# PIC_WIFI.net
KiCad netlist of a schematic drawn in EAGLE
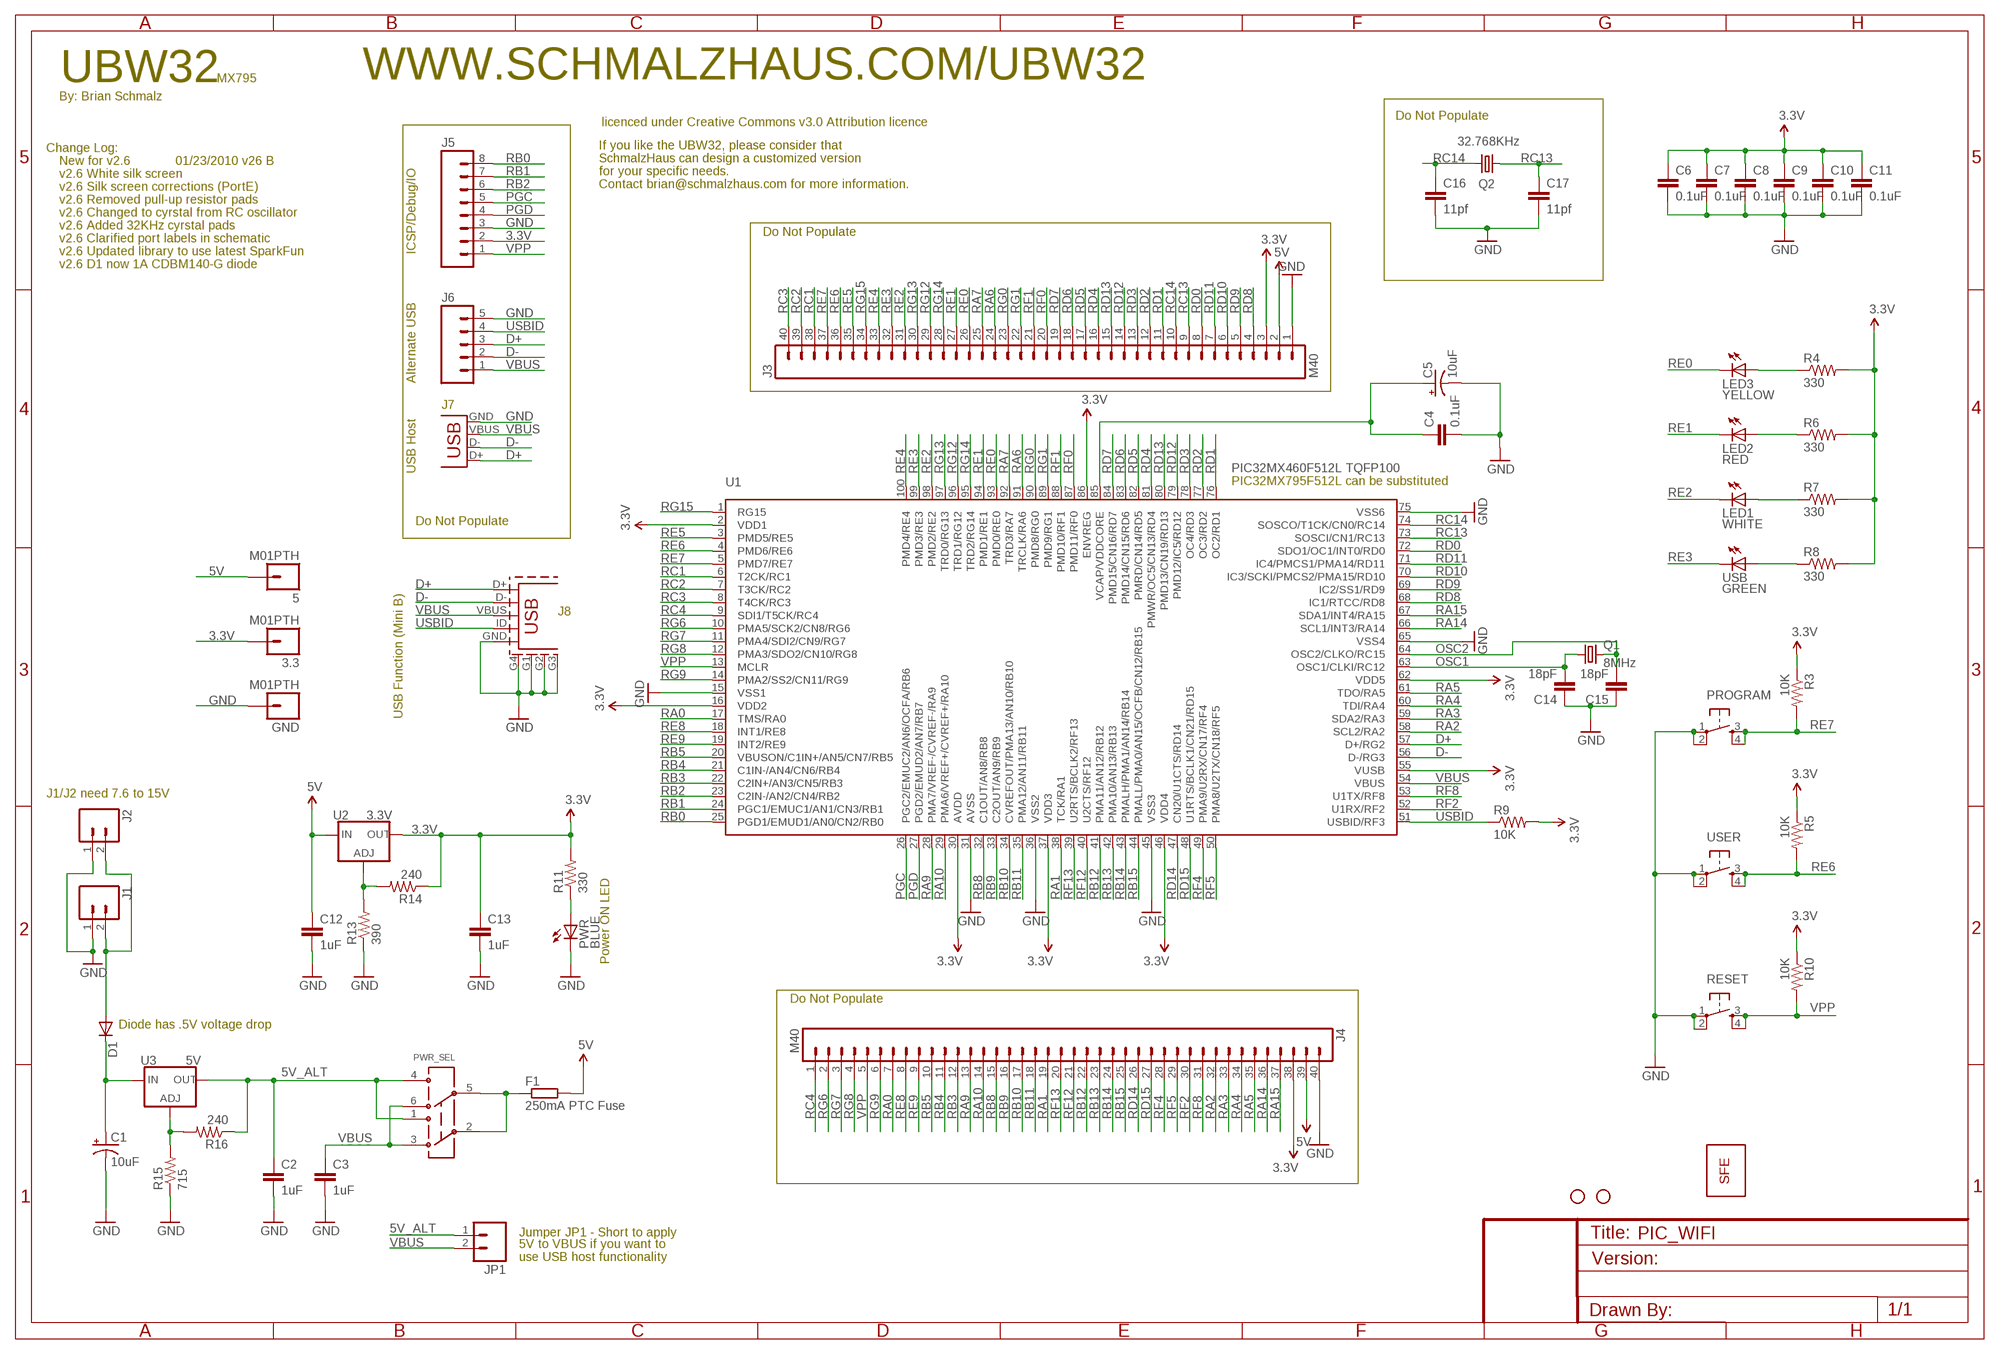
[diagram p0: schematic, sheet 1]

(export (version "E")
  (design (tool "Eeschema 10.0.6"))
  (components
    (comp (ref "3.3")
      (value "M01PTH")
      (footprint "eagle-import:1X01")
      (libsource (lib "eagle-import") (part "M01PTH"))
    )
    (comp (ref "5")
      (value "M01PTH")
      (footprint "eagle-import:1X01")
      (libsource (lib "eagle-import") (part "M01PTH"))
    )
    (comp (ref "C1")
      (value "10uF")
      (footprint "eagle-import:EIA3528")
      (libsource (lib "eagle-import") (part "CAP_POL3528"))
    )
    (comp (ref "C2")
      (value "1uF")
      (footprint "eagle-import:C0402")
      (libsource (lib "eagle-import") (part "CAP0402"))
    )
    (comp (ref "C3")
      (value "1uF")
      (footprint "eagle-import:C0402")
      (libsource (lib "eagle-import") (part "CAP0402"))
    )
    (comp (ref "C4")
      (value "0.1uF")
      (footprint "eagle-import:C0402")
      (libsource (lib "eagle-import") (part "CAP0402"))
    )
    (comp (ref "C5")
      (value "10uF")
      (footprint "eagle-import:EIA3528")
      (libsource (lib "eagle-import") (part "CAP_POL3528"))
    )
    (comp (ref "C6")
      (value "0.1uF")
      (footprint "eagle-import:C0402")
      (libsource (lib "eagle-import") (part "CAP0402"))
    )
    (comp (ref "C7")
      (value "0.1uF")
      (footprint "eagle-import:C0402")
      (libsource (lib "eagle-import") (part "CAP0402"))
    )
    (comp (ref "C8")
      (value "0.1uF")
      (footprint "eagle-import:C0402")
      (libsource (lib "eagle-import") (part "CAP0402"))
    )
    (comp (ref "C9")
      (value "0.1uF")
      (footprint "eagle-import:C0402")
      (libsource (lib "eagle-import") (part "CAP0402"))
    )
    (comp (ref "C10")
      (value "0.1uF")
      (footprint "eagle-import:C0402")
      (libsource (lib "eagle-import") (part "SparkFun02-20-08_CAP0402"))
    )
    (comp (ref "C11")
      (value "0.1uF")
      (footprint "eagle-import:C0402")
      (libsource (lib "eagle-import") (part "CAP0402"))
    )
    (comp (ref "C12")
      (value "1uF")
      (footprint "eagle-import:C0402")
      (libsource (lib "eagle-import") (part "SparkFun02-20-08_CAP0402"))
    )
    (comp (ref "C13")
      (value "1uF")
      (footprint "eagle-import:C0402")
      (libsource (lib "eagle-import") (part "SparkFun02-20-08_CAP0402"))
    )
    (comp (ref "C14")
      (value "18pF")
      (footprint "eagle-import:C0402")
      (libsource (lib "eagle-import") (part "CAP0402"))
    )
    (comp (ref "C15")
      (value "18pF")
      (footprint "eagle-import:C0402")
      (libsource (lib "eagle-import") (part "CAP0402"))
    )
    (comp (ref "C16")
      (value "11pf")
      (footprint "eagle-import:C0402")
      (libsource (lib "eagle-import") (part "CAP0402"))
    )
    (comp (ref "C17")
      (value "11pf")
      (footprint "eagle-import:C0402")
      (libsource (lib "eagle-import") (part "CAP0402"))
    )
    (comp (ref "D1")
      (value "DIODESMA")
      (footprint "eagle-import:SMA-DIODE")
      (libsource (lib "eagle-import") (part "DIODESMA"))
    )
    (comp (ref "F1")
      (value "250mA PTC Fuse")
      (footprint "eagle-import:R1206")
      (libsource (lib "eagle-import") (part "R-EU_R1206"))
    )
    (comp (ref "GND")
      (value "M01PTH")
      (footprint "eagle-import:1X01")
      (libsource (lib "eagle-import") (part "M01PTH"))
    )
    (comp (ref "J1")
      (value "M02PTH")
      (footprint "eagle-import:1X02")
      (libsource (lib "eagle-import") (part "SparkFun-12-01-09_M02PTH"))
    )
    (comp (ref "J2")
      (value "M02-JST-2MM-SMT")
      (footprint "eagle-import:S2B-PH")
      (libsource (lib "eagle-import") (part "M02-JST-2MM-SMT"))
    )
    (comp (ref "J3")
      (value "M40")
      (footprint "eagle-import:1X40")
      (libsource (lib "eagle-import") (part "M40"))
    )
    (comp (ref "J4")
      (value "M40")
      (footprint "eagle-import:1X40")
      (libsource (lib "eagle-import") (part "M40"))
    )
    (comp (ref "J5")
      (value "M08")
      (footprint "eagle-import:1X08")
      (libsource (lib "eagle-import") (part "M08"))
    )
    (comp (ref "J6")
      (value "M05PTH")
      (footprint "eagle-import:1X05")
      (libsource (lib "eagle-import") (part "M05PTH"))
    )
    (comp (ref "J7")
      (value "USB-A-S")
      (footprint "eagle-import:USB-A-S")
      (libsource (lib "eagle-import") (part "USB-A-S"))
    )
    (comp (ref "J8")
      (value "USB_5PIN")
      (footprint "eagle-import:USB-MINIB")
      (libsource (lib "eagle-import") (part "USB_5PIN"))
    )
    (comp (ref "JP1")
      (value "M02PTH")
      (footprint "eagle-import:1X02")
      (libsource (lib "eagle-import") (part "SparkFun-12-01-09_M02PTH"))
    )
    (comp (ref "LED1")
      (value "WHITE")
      (footprint "eagle-import:LED-0603")
      (libsource (lib "eagle-import") (part "LED0603"))
    )
    (comp (ref "LED2")
      (value "RED")
      (footprint "eagle-import:LED-0603")
      (libsource (lib "eagle-import") (part "LED0603"))
    )
    (comp (ref "LED3")
      (value "YELLOW")
      (footprint "eagle-import:LED-0603")
      (libsource (lib "eagle-import") (part "LED0603"))
    )
    (comp (ref "PROGRAM")
      (value "TAC_SWITCHSND")
      (footprint "eagle-import:TACTILE_SWITCH_SMD")
      (libsource (lib "eagle-import") (part "TAC_SWITCHSND"))
    )
    (comp (ref "PWR")
      (value "BLUE")
      (footprint "eagle-import:LED-0603")
      (libsource (lib "eagle-import") (part "LED0603"))
    )
    (comp (ref "PWR_SEL")
      (value "AYZ0202")
      (footprint "eagle-import:AYZ0202")
      (libsource (lib "eagle-import") (part "AYZ0202"))
    )
    (comp (ref "Q1")
      (value "8MHz")
      (footprint "eagle-import:CRYSTAL-SMD-5X3")
      (libsource (lib "eagle-import") (part "SparkFun11_03_09_CRYSTAL5X3"))
    )
    (comp (ref "Q2")
      (value "32.768KHz")
      (footprint "eagle-import:CRYSTAL-32KHZ-SMD")
      (libsource (lib "eagle-import") (part "CRYSTAL32-SMD"))
    )
    (comp (ref "R3")
      (value "10K")
      (footprint "eagle-import:C0402")
      (libsource (lib "eagle-import") (part "RESISTOR0402"))
    )
    (comp (ref "R4")
      (value "330")
      (footprint "eagle-import:C0402")
      (libsource (lib "eagle-import") (part "RESISTOR0402"))
    )
    (comp (ref "R5")
      (value "10K")
      (footprint "eagle-import:C0402")
      (libsource (lib "eagle-import") (part "RESISTOR0402"))
    )
    (comp (ref "R6")
      (value "330")
      (footprint "eagle-import:C0402")
      (libsource (lib "eagle-import") (part "RESISTOR0402"))
    )
    (comp (ref "R7")
      (value "330")
      (footprint "eagle-import:C0402")
      (libsource (lib "eagle-import") (part "RESISTOR0402"))
    )
    (comp (ref "R8")
      (value "330")
      (footprint "eagle-import:C0402")
      (libsource (lib "eagle-import") (part "RESISTOR0402"))
    )
    (comp (ref "R9")
      (value "10K")
      (footprint "eagle-import:C0402")
      (libsource (lib "eagle-import") (part "RESISTOR0402"))
    )
    (comp (ref "R10")
      (value "10K")
      (footprint "eagle-import:C0402")
      (libsource (lib "eagle-import") (part "RESISTOR0402"))
    )
    (comp (ref "R11")
      (value "330")
      (footprint "eagle-import:C0402")
      (libsource (lib "eagle-import") (part "RESISTOR0402"))
    )
    (comp (ref "R13")
      (value "390")
      (footprint "eagle-import:C0402")
      (libsource (lib "eagle-import") (part "RESISTOR0402"))
    )
    (comp (ref "R14")
      (value "240")
      (footprint "eagle-import:C0402")
      (libsource (lib "eagle-import") (part "RESISTOR0402"))
    )
    (comp (ref "R15")
      (value "715")
      (footprint "eagle-import:C0402")
      (libsource (lib "eagle-import") (part "RESISTOR0402"))
    )
    (comp (ref "R16")
      (value "240")
      (footprint "eagle-import:C0402")
      (libsource (lib "eagle-import") (part "RESISTOR0402"))
    )
    (comp (ref "RESET")
      (value "TAC_SWITCHSND")
      (footprint "eagle-import:TACTILE_SWITCH_SMD")
      (libsource (lib "eagle-import") (part "TAC_SWITCHSND"))
    )
    (comp (ref "U$4")
      (value "LOGO-SFENEW")
      (footprint "eagle-import:SFE-NEW-WEBLOGO")
      (libsource (lib "eagle-import") (part "LOGO-SFENEW"))
    )
    (comp (ref "U$6")
      (value "STAND-OFF")
      (footprint "eagle-import:STAND-OFF")
      (libsource (lib "eagle-import") (part "STAND-OFF"))
    )
    (comp (ref "U$7")
      (value "STAND-OFF")
      (footprint "eagle-import:STAND-OFF")
      (libsource (lib "eagle-import") (part "STAND-OFF"))
    )
    (comp (ref "U1")
      (value "PIC32MX460F512L TQFP100")
      (footprint "eagle-import:TQFP100")
      (libsource (lib "eagle-import") (part "PIC32MX4XXLTQFP100"))
    )
    (comp (ref "U2")
      (value "3.3V")
      (footprint "eagle-import:SOT223")
      (libsource (lib "eagle-import") (part "V_REG_317SMD"))
    )
    (comp (ref "U3")
      (value "5V")
      (footprint "eagle-import:SOT223")
      (libsource (lib "eagle-import") (part "V_REG_317SMD"))
    )
    (comp (ref "USB")
      (value "GREEN")
      (footprint "eagle-import:LED-0603")
      (libsource (lib "eagle-import") (part "LED0603"))
    )
    (comp (ref "USER")
      (value "TAC_SWITCHSND")
      (footprint "eagle-import:TACTILE_SWITCH_SMD")
      (libsource (lib "eagle-import") (part "TAC_SWITCHSND"))
    )
  )
  (nets
    (net (code "1") (name "/5V_ALT") (class "Default")
      (node (ref "C2") (pin "1") (pinfunction "1_1") (pintype "passive"))
      (node (ref "JP1") (pin "1") (pinfunction "1_1") (pintype "passive"))
      (node (ref "PWR_SEL") (pin "1") (pinfunction "3_1") (pintype "bidirectional"))
      (node (ref "PWR_SEL") (pin "4") (pinfunction "6_4") (pintype "bidirectional"))
      (node (ref "R16") (pin "1") (pinfunction "1_1") (pintype "passive"))
      (node (ref "U3") (pin "2") (pinfunction "OUT_2") (pintype "output"))
    )
    (net (code "2") (name "/D+") (class "Default")
      (node (ref "J6") (pin "3") (pinfunction "3_3") (pintype "passive"))
      (node (ref "J7") (pin "D+") (pinfunction "D+_D+") (pintype "bidirectional"))
      (node (ref "J8") (pin "D+") (pinfunction "D+_D+") (pintype "bidirectional"))
      (node (ref "U1") (pin "57") (pinfunction "D+/RG2_57") (pintype "bidirectional"))
    )
    (net (code "3") (name "/D-") (class "Default")
      (node (ref "J6") (pin "2") (pinfunction "2_2") (pintype "passive"))
      (node (ref "J7") (pin "D-") (pinfunction "D-_D-") (pintype "bidirectional"))
      (node (ref "J8") (pin "D-") (pinfunction "D-_D-") (pintype "bidirectional"))
      (node (ref "U1") (pin "56") (pinfunction "D-/RG3_56") (pintype "bidirectional"))
    )
    (net (code "4") (name "/OSC1") (class "Default")
      (node (ref "C14") (pin "2") (pinfunction "2_2") (pintype "passive"))
      (node (ref "Q1") (pin "1") (pinfunction "1_1") (pintype "passive"))
      (node (ref "U1") (pin "63") (pinfunction "OSC1/CLKI/RC12_63") (pintype "bidirectional"))
    )
    (net (code "5") (name "/OSC2") (class "Default")
      (node (ref "C15") (pin "2") (pinfunction "2_2") (pintype "passive"))
      (node (ref "Q1") (pin "3") (pinfunction "2_3") (pintype "passive"))
      (node (ref "U1") (pin "64") (pinfunction "OSC2/CLKO/RC15_64") (pintype "bidirectional"))
    )
    (net (code "6") (name "/PGC") (class "Default")
      (node (ref "J5") (pin "5") (pinfunction "5_5") (pintype "passive"))
      (node (ref "U1") (pin "26") (pinfunction "PGC2/EMUC2/AN6/OCFA/RB6_26") (pintype "bidirectional"))
    )
    (net (code "7") (name "/PGD") (class "Default")
      (node (ref "J5") (pin "4") (pinfunction "4_4") (pintype "passive"))
      (node (ref "U1") (pin "27") (pinfunction "PGD2/EMUD2/AN7/RB7_27") (pintype "bidirectional"))
    )
    (net (code "8") (name "/RA0") (class "Default")
      (node (ref "J4") (pin "7") (pinfunction "7_7") (pintype "passive"))
      (node (ref "U1") (pin "17") (pinfunction "TMS/RA0_17") (pintype "bidirectional"))
    )
    (net (code "9") (name "/RA1") (class "Default")
      (node (ref "J4") (pin "19") (pinfunction "19_19") (pintype "passive"))
      (node (ref "U1") (pin "38") (pinfunction "TCK/RA1_38") (pintype "bidirectional"))
    )
    (net (code "10") (name "/RA2") (class "Default")
      (node (ref "J4") (pin "32") (pinfunction "32_32") (pintype "passive"))
      (node (ref "U1") (pin "58") (pinfunction "SCL2/RA2_58") (pintype "bidirectional"))
    )
    (net (code "11") (name "/RA3") (class "Default")
      (node (ref "J4") (pin "33") (pinfunction "33_33") (pintype "passive"))
      (node (ref "U1") (pin "59") (pinfunction "SDA2/RA3_59") (pintype "bidirectional"))
    )
    (net (code "12") (name "/RA4") (class "Default")
      (node (ref "J4") (pin "34") (pinfunction "34_34") (pintype "passive"))
      (node (ref "U1") (pin "60") (pinfunction "TDI/RA4_60") (pintype "bidirectional"))
    )
    (net (code "13") (name "/RA5") (class "Default")
      (node (ref "J4") (pin "35") (pinfunction "35_35") (pintype "passive"))
      (node (ref "U1") (pin "61") (pinfunction "TDO/RA5_61") (pintype "bidirectional"))
    )
    (net (code "14") (name "/RA6") (class "Default")
      (node (ref "J3") (pin "24") (pinfunction "24_24") (pintype "passive"))
      (node (ref "U1") (pin "91") (pinfunction "TRCLK/RA6_91") (pintype "bidirectional"))
    )
    (net (code "15") (name "/RA7") (class "Default")
      (node (ref "J3") (pin "25") (pinfunction "25_25") (pintype "passive"))
      (node (ref "U1") (pin "92") (pinfunction "TRD3/RA7_92") (pintype "bidirectional"))
    )
    (net (code "16") (name "/RA9") (class "Default")
      (node (ref "J4") (pin "13") (pinfunction "13_13") (pintype "passive"))
      (node (ref "U1") (pin "28") (pinfunction "PMA7/VREF-/CVREF-/RA9_28") (pintype "bidirectional"))
    )
    (net (code "17") (name "/RA10") (class "Default")
      (node (ref "J4") (pin "14") (pinfunction "14_14") (pintype "passive"))
      (node (ref "U1") (pin "29") (pinfunction "PMA6/VREF+/CVREF+/RA10_29") (pintype "bidirectional"))
    )
    (net (code "18") (name "/RA14") (class "Default")
      (node (ref "J4") (pin "36") (pinfunction "36_36") (pintype "passive"))
      (node (ref "U1") (pin "66") (pinfunction "SCL1/INT3/RA14_66") (pintype "bidirectional"))
    )
    (net (code "19") (name "/RA15") (class "Default")
      (node (ref "J4") (pin "37") (pinfunction "37_37") (pintype "passive"))
      (node (ref "U1") (pin "67") (pinfunction "SDA1/INT4/RA15_67") (pintype "bidirectional"))
    )
    (net (code "20") (name "/RB0") (class "Default")
      (node (ref "J5") (pin "8") (pinfunction "8_8") (pintype "passive"))
      (node (ref "U1") (pin "25") (pinfunction "PGD1/EMUD1/AN0/CN2/RB0_25") (pintype "bidirectional"))
    )
    (net (code "21") (name "/RB1") (class "Default")
      (node (ref "J5") (pin "7") (pinfunction "7_7") (pintype "passive"))
      (node (ref "U1") (pin "24") (pinfunction "PGC1/EMUC1/AN1/CN3/RB1_24") (pintype "bidirectional"))
    )
    (net (code "22") (name "/RB2") (class "Default")
      (node (ref "J5") (pin "6") (pinfunction "6_6") (pintype "passive"))
      (node (ref "U1") (pin "23") (pinfunction "C2IN-/AN2/CN4/RB2_23") (pintype "bidirectional"))
    )
    (net (code "23") (name "/RB3") (class "Default")
      (node (ref "J4") (pin "12") (pinfunction "12_12") (pintype "passive"))
      (node (ref "U1") (pin "22") (pinfunction "C2IN+/AN3/CN5/RB3_22") (pintype "bidirectional"))
    )
    (net (code "24") (name "/RB4") (class "Default")
      (node (ref "J4") (pin "11") (pinfunction "11_11") (pintype "passive"))
      (node (ref "U1") (pin "21") (pinfunction "C1IN-/AN4/CN6/RB4_21") (pintype "bidirectional"))
    )
    (net (code "25") (name "/RB5") (class "Default")
      (node (ref "J4") (pin "10") (pinfunction "10_10") (pintype "passive"))
      (node (ref "U1") (pin "20") (pinfunction "VBUSON/C1IN+/AN5/CN7/RB5_20") (pintype "bidirectional"))
    )
    (net (code "26") (name "/RB8") (class "Default")
      (node (ref "J4") (pin "15") (pinfunction "15_15") (pintype "passive"))
      (node (ref "U1") (pin "32") (pinfunction "C1OUT/AN8/RB8_32") (pintype "bidirectional"))
    )
    (net (code "27") (name "/RB9") (class "Default")
      (node (ref "J4") (pin "16") (pinfunction "16_16") (pintype "passive"))
      (node (ref "U1") (pin "33") (pinfunction "C2OUT/AN9/RB9_33") (pintype "bidirectional"))
    )
    (net (code "28") (name "/RB10") (class "Default")
      (node (ref "J4") (pin "17") (pinfunction "17_17") (pintype "passive"))
      (node (ref "U1") (pin "34") (pinfunction "CVREFOUT/PMA13/AN10/RB10_34") (pintype "bidirectional"))
    )
    (net (code "29") (name "/RB11") (class "Default")
      (node (ref "J4") (pin "18") (pinfunction "18_18") (pintype "passive"))
      (node (ref "U1") (pin "35") (pinfunction "PMA12/AN11/RB11_35") (pintype "bidirectional"))
    )
    (net (code "30") (name "/RB12") (class "Default")
      (node (ref "J4") (pin "22") (pinfunction "22_22") (pintype "passive"))
      (node (ref "U1") (pin "41") (pinfunction "PMA11/AN12/RB12_41") (pintype "bidirectional"))
    )
    (net (code "31") (name "/RB13") (class "Default")
      (node (ref "J4") (pin "23") (pinfunction "23_23") (pintype "passive"))
      (node (ref "U1") (pin "42") (pinfunction "PMA10/AN13/RB13_42") (pintype "bidirectional"))
    )
    (net (code "32") (name "/RB14") (class "Default")
      (node (ref "J4") (pin "24") (pinfunction "24_24") (pintype "passive"))
      (node (ref "U1") (pin "43") (pinfunction "PMALH/PMA1/AN14/RB14_43") (pintype "bidirectional"))
    )
    (net (code "33") (name "/RB15") (class "Default")
      (node (ref "J4") (pin "25") (pinfunction "25_25") (pintype "passive"))
      (node (ref "U1") (pin "44") (pinfunction "PMALL/PMA0/AN15/OCFB/CN12/RB15_44") (pintype "bidirectional"))
    )
    (net (code "34") (name "/RC1") (class "Default")
      (node (ref "J3") (pin "38") (pinfunction "38_38") (pintype "passive"))
      (node (ref "U1") (pin "6") (pinfunction "T2CK/RC1_6") (pintype "bidirectional"))
    )
    (net (code "35") (name "/RC2") (class "Default")
      (node (ref "J3") (pin "39") (pinfunction "39_39") (pintype "passive"))
      (node (ref "U1") (pin "7") (pinfunction "T3CK/RC2_7") (pintype "bidirectional"))
    )
    (net (code "36") (name "/RC3") (class "Default")
      (node (ref "J3") (pin "40") (pinfunction "40_40") (pintype "passive"))
      (node (ref "U1") (pin "8") (pinfunction "T4CK/RC3_8") (pintype "bidirectional"))
    )
    (net (code "37") (name "/RC4") (class "Default")
      (node (ref "J4") (pin "1") (pinfunction "1_1") (pintype "passive"))
      (node (ref "U1") (pin "9") (pinfunction "SDI1/T5CK/RC4_9") (pintype "bidirectional"))
    )
    (net (code "38") (name "/RC13") (class "Default")
      (node (ref "C17") (pin "1") (pinfunction "1_1") (pintype "passive"))
      (node (ref "J3") (pin "9") (pinfunction "9_9") (pintype "passive"))
      (node (ref "Q2") (pin "X1") (pinfunction "1_X1") (pintype "passive"))
      (node (ref "U1") (pin "73") (pinfunction "SOSCI/CN1/RC13_73") (pintype "bidirectional"))
    )
    (net (code "39") (name "/RC14") (class "Default")
      (node (ref "C16") (pin "1") (pinfunction "1_1") (pintype "passive"))
      (node (ref "J3") (pin "10") (pinfunction "10_10") (pintype "passive"))
      (node (ref "Q2") (pin "X2") (pinfunction "2_X2") (pintype "passive"))
      (node (ref "U1") (pin "74") (pinfunction "SOSCO/T1CK/CN0/RC14_74") (pintype "bidirectional"))
    )
    (net (code "40") (name "/RD0") (class "Default")
      (node (ref "J3") (pin "8") (pinfunction "8_8") (pintype "passive"))
      (node (ref "U1") (pin "72") (pinfunction "SDO1/OC1/INT0/RD0_72") (pintype "bidirectional"))
    )
    (net (code "41") (name "/RD1") (class "Default")
      (node (ref "J3") (pin "11") (pinfunction "11_11") (pintype "passive"))
      (node (ref "U1") (pin "76") (pinfunction "OC2/RD1_76") (pintype "bidirectional"))
    )
    (net (code "42") (name "/RD2") (class "Default")
      (node (ref "J3") (pin "12") (pinfunction "12_12") (pintype "passive"))
      (node (ref "U1") (pin "77") (pinfunction "OC3/RD2_77") (pintype "bidirectional"))
    )
    (net (code "43") (name "/RD3") (class "Default")
      (node (ref "J3") (pin "13") (pinfunction "13_13") (pintype "passive"))
      (node (ref "U1") (pin "78") (pinfunction "OC4/RD3_78") (pintype "bidirectional"))
    )
    (net (code "44") (name "/RD4") (class "Default")
      (node (ref "J3") (pin "16") (pinfunction "16_16") (pintype "passive"))
      (node (ref "U1") (pin "81") (pinfunction "PMWR/OC5/CN13/RD4_81") (pintype "bidirectional"))
    )
    (net (code "45") (name "/RD5") (class "Default")
      (node (ref "J3") (pin "17") (pinfunction "17_17") (pintype "passive"))
      (node (ref "U1") (pin "82") (pinfunction "PMRD/CN14/RD5_82") (pintype "bidirectional"))
    )
    (net (code "46") (name "/RD6") (class "Default")
      (node (ref "J3") (pin "18") (pinfunction "18_18") (pintype "passive"))
      (node (ref "U1") (pin "83") (pinfunction "PMD14/CN15/RD6_83") (pintype "bidirectional"))
    )
    (net (code "47") (name "/RD7") (class "Default")
      (node (ref "J3") (pin "19") (pinfunction "19_19") (pintype "passive"))
      (node (ref "U1") (pin "84") (pinfunction "PMD15/CN16/RD7_84") (pintype "bidirectional"))
    )
    (net (code "48") (name "/RD8") (class "Default")
      (node (ref "J3") (pin "4") (pinfunction "4_4") (pintype "passive"))
      (node (ref "U1") (pin "68") (pinfunction "IC1/RTCC/RD8_68") (pintype "bidirectional"))
    )
    (net (code "49") (name "/RD9") (class "Default")
      (node (ref "J3") (pin "5") (pinfunction "5_5") (pintype "passive"))
      (node (ref "U1") (pin "69") (pinfunction "IC2/SS1/RD9_69") (pintype "bidirectional"))
    )
    (net (code "50") (name "/RD10") (class "Default")
      (node (ref "J3") (pin "6") (pinfunction "6_6") (pintype "passive"))
      (node (ref "U1") (pin "70") (pinfunction "IC3/SCKI/PMCS2/PMA15/RD10_70") (pintype "bidirectional"))
    )
    (net (code "51") (name "/RD11") (class "Default")
      (node (ref "J3") (pin "7") (pinfunction "7_7") (pintype "passive"))
      (node (ref "U1") (pin "71") (pinfunction "IC4/PMCS1/PMA14/RD11_71") (pintype "bidirectional"))
    )
    (net (code "52") (name "/RD12") (class "Default")
      (node (ref "J3") (pin "14") (pinfunction "14_14") (pintype "passive"))
      (node (ref "U1") (pin "79") (pinfunction "PMD12/IC5/RD12_79") (pintype "bidirectional"))
    )
    (net (code "53") (name "/RD13") (class "Default")
      (node (ref "J3") (pin "15") (pinfunction "15_15") (pintype "passive"))
      (node (ref "U1") (pin "80") (pinfunction "PMD13/CN19/RD13_80") (pintype "bidirectional"))
    )
    (net (code "54") (name "/RD14") (class "Default")
      (node (ref "J4") (pin "26") (pinfunction "26_26") (pintype "passive"))
      (node (ref "U1") (pin "47") (pinfunction "CN20/U1CTS/RD14_47") (pintype "bidirectional"))
    )
    (net (code "55") (name "/RD15") (class "Default")
      (node (ref "J4") (pin "27") (pinfunction "27_27") (pintype "passive"))
      (node (ref "U1") (pin "48") (pinfunction "U1RTS/BCLK1/CN21/RD15_48") (pintype "bidirectional"))
    )
    (net (code "56") (name "/RE0") (class "Default")
      (node (ref "J3") (pin "26") (pinfunction "26_26") (pintype "passive"))
      (node (ref "LED3") (pin "C") (pinfunction "C_C") (pintype "passive"))
      (node (ref "U1") (pin "93") (pinfunction "PMD0/RE0_93") (pintype "bidirectional"))
    )
    (net (code "57") (name "/RE1") (class "Default")
      (node (ref "J3") (pin "27") (pinfunction "27_27") (pintype "passive"))
      (node (ref "LED2") (pin "C") (pinfunction "C_C") (pintype "passive"))
      (node (ref "U1") (pin "94") (pinfunction "PMD1/RE1_94") (pintype "bidirectional"))
    )
    (net (code "58") (name "/RE2") (class "Default")
      (node (ref "J3") (pin "31") (pinfunction "31_31") (pintype "passive"))
      (node (ref "LED1") (pin "C") (pinfunction "C_C") (pintype "passive"))
      (node (ref "U1") (pin "98") (pinfunction "PMD2/RE2_98") (pintype "bidirectional"))
    )
    (net (code "59") (name "/RE3") (class "Default")
      (node (ref "J3") (pin "32") (pinfunction "32_32") (pintype "passive"))
      (node (ref "U1") (pin "99") (pinfunction "PMD3/RE3_99") (pintype "bidirectional"))
      (node (ref "USB") (pin "C") (pinfunction "C_C") (pintype "passive"))
    )
    (net (code "60") (name "/RE4") (class "Default")
      (node (ref "J3") (pin "33") (pinfunction "33_33") (pintype "passive"))
      (node (ref "U1") (pin "100") (pinfunction "PMD4/RE4_100") (pintype "bidirectional"))
    )
    (net (code "61") (name "/RE5") (class "Default")
      (node (ref "J3") (pin "35") (pinfunction "35_35") (pintype "passive"))
      (node (ref "U1") (pin "3") (pinfunction "PMD5/RE5_3") (pintype "bidirectional"))
    )
    (net (code "62") (name "/RE6") (class "Default")
      (node (ref "J3") (pin "36") (pinfunction "36_36") (pintype "passive"))
      (node (ref "R5") (pin "2") (pinfunction "2_2") (pintype "passive"))
      (node (ref "U1") (pin "4") (pinfunction "PMD6/RE6_4") (pintype "bidirectional"))
      (node (ref "USER") (pin "3") (pinfunction "3_3") (pintype "passive"))
      (node (ref "USER") (pin "4") (pinfunction "4_4") (pintype "passive"))
    )
    (net (code "63") (name "/RE7") (class "Default")
      (node (ref "J3") (pin "37") (pinfunction "37_37") (pintype "passive"))
      (node (ref "PROGRAM") (pin "3") (pinfunction "3_3") (pintype "passive"))
      (node (ref "PROGRAM") (pin "4") (pinfunction "4_4") (pintype "passive"))
      (node (ref "R3") (pin "2") (pinfunction "2_2") (pintype "passive"))
      (node (ref "U1") (pin "5") (pinfunction "PMD7/RE7_5") (pintype "bidirectional"))
    )
    (net (code "64") (name "/RE8") (class "Default")
      (node (ref "J4") (pin "8") (pinfunction "8_8") (pintype "passive"))
      (node (ref "U1") (pin "18") (pinfunction "INT1/RE8_18") (pintype "bidirectional"))
    )
    (net (code "65") (name "/RE9") (class "Default")
      (node (ref "J4") (pin "9") (pinfunction "9_9") (pintype "passive"))
      (node (ref "U1") (pin "19") (pinfunction "INT2/RE9_19") (pintype "bidirectional"))
    )
    (net (code "66") (name "/RF0") (class "Default")
      (node (ref "J3") (pin "20") (pinfunction "20_20") (pintype "passive"))
      (node (ref "U1") (pin "87") (pinfunction "PMD11/RF0_87") (pintype "bidirectional"))
    )
    (net (code "67") (name "/RF1") (class "Default")
      (node (ref "J3") (pin "21") (pinfunction "21_21") (pintype "passive"))
      (node (ref "U1") (pin "88") (pinfunction "PMD10/RF1_88") (pintype "bidirectional"))
    )
    (net (code "68") (name "/RF2") (class "Default")
      (node (ref "J4") (pin "30") (pinfunction "30_30") (pintype "passive"))
      (node (ref "U1") (pin "52") (pinfunction "U1RX/RF2_52") (pintype "bidirectional"))
    )
    (net (code "69") (name "/RF4") (class "Default")
      (node (ref "J4") (pin "28") (pinfunction "28_28") (pintype "passive"))
      (node (ref "U1") (pin "49") (pinfunction "PMA9/U2RX/CN17/RF4_49") (pintype "bidirectional"))
    )
    (net (code "70") (name "/RF5") (class "Default")
      (node (ref "J4") (pin "29") (pinfunction "29_29") (pintype "passive"))
      (node (ref "U1") (pin "50") (pinfunction "PMA8/U2TX/CN18/RF5_50") (pintype "bidirectional"))
    )
    (net (code "71") (name "/RF8") (class "Default")
      (node (ref "J4") (pin "31") (pinfunction "31_31") (pintype "passive"))
      (node (ref "U1") (pin "53") (pinfunction "U1TX/RF8_53") (pintype "bidirectional"))
    )
    (net (code "72") (name "/RF12") (class "Default")
      (node (ref "J4") (pin "21") (pinfunction "21_21") (pintype "passive"))
      (node (ref "U1") (pin "40") (pinfunction "U2CTS/RF12_40") (pintype "bidirectional"))
    )
    (net (code "73") (name "/RF13") (class "Default")
      (node (ref "J4") (pin "20") (pinfunction "20_20") (pintype "passive"))
      (node (ref "U1") (pin "39") (pinfunction "U2RTS/BCLK2/RF13_39") (pintype "bidirectional"))
    )
    (net (code "74") (name "/RG0") (class "Default")
      (node (ref "J3") (pin "23") (pinfunction "23_23") (pintype "passive"))
      (node (ref "U1") (pin "90") (pinfunction "PMD8/RG0_90") (pintype "bidirectional"))
    )
    (net (code "75") (name "/RG1") (class "Default")
      (node (ref "J3") (pin "22") (pinfunction "22_22") (pintype "passive"))
      (node (ref "U1") (pin "89") (pinfunction "PMD9/RG1_89") (pintype "bidirectional"))
    )
    (net (code "76") (name "/RG6") (class "Default")
      (node (ref "J4") (pin "2") (pinfunction "2_2") (pintype "passive"))
      (node (ref "U1") (pin "10") (pinfunction "PMA5/SCK2/CN8/RG6_10") (pintype "bidirectional"))
    )
    (net (code "77") (name "/RG7") (class "Default")
      (node (ref "J4") (pin "3") (pinfunction "3_3") (pintype "passive"))
      (node (ref "U1") (pin "11") (pinfunction "PMA4/SDI2/CN9/RG7_11") (pintype "bidirectional"))
    )
    (net (code "78") (name "/RG8") (class "Default")
      (node (ref "J4") (pin "4") (pinfunction "4_4") (pintype "passive"))
      (node (ref "U1") (pin "12") (pinfunction "PMA3/SDO2/CN10/RG8_12") (pintype "bidirectional"))
    )
    (net (code "79") (name "/RG9") (class "Default")
      (node (ref "J4") (pin "6") (pinfunction "6_6") (pintype "passive"))
      (node (ref "U1") (pin "14") (pinfunction "PMA2/SS2/CN11/RG9_14") (pintype "bidirectional"))
    )
    (net (code "80") (name "/RG12") (class "Default")
      (node (ref "J3") (pin "29") (pinfunction "29_29") (pintype "passive"))
      (node (ref "U1") (pin "96") (pinfunction "TRD1/RG12_96") (pintype "bidirectional"))
    )
    (net (code "81") (name "/RG13") (class "Default")
      (node (ref "J3") (pin "30") (pinfunction "30_30") (pintype "passive"))
      (node (ref "U1") (pin "97") (pinfunction "TRD0/RG13_97") (pintype "bidirectional"))
    )
    (net (code "82") (name "/RG14") (class "Default")
      (node (ref "J3") (pin "28") (pinfunction "28_28") (pintype "passive"))
      (node (ref "U1") (pin "95") (pinfunction "TRD2/RG14_95") (pintype "bidirectional"))
    )
    (net (code "83") (name "/RG15") (class "Default")
      (node (ref "J3") (pin "34") (pinfunction "34_34") (pintype "passive"))
      (node (ref "U1") (pin "1") (pinfunction "RG15_1") (pintype "bidirectional"))
    )
    (net (code "84") (name "/USBID") (class "Default")
      (node (ref "J6") (pin "4") (pinfunction "4_4") (pintype "passive"))
      (node (ref "J8") (pin "ID") (pinfunction "USB_ID_ID") (pintype "bidirectional"))
      (node (ref "R9") (pin "1") (pinfunction "1_1") (pintype "passive"))
      (node (ref "U1") (pin "51") (pinfunction "USBID/RF3_51") (pintype "bidirectional"))
    )
    (net (code "85") (name "/VBUS") (class "Default")
      (node (ref "C3") (pin "1") (pinfunction "1_1") (pintype "passive"))
      (node (ref "J6") (pin "1") (pinfunction "1_1") (pintype "passive"))
      (node (ref "J7") (pin "VBUS") (pinfunction "VBUS_VBUS") (pintype "bidirectional"))
      (node (ref "J8") (pin "VBUS") (pinfunction "VBUS_VBUS") (pintype "bidirectional"))
      (node (ref "JP1") (pin "2") (pinfunction "2_2") (pintype "passive"))
      (node (ref "PWR_SEL") (pin "3") (pinfunction "1_3") (pintype "bidirectional"))
      (node (ref "PWR_SEL") (pin "6") (pinfunction "4_6") (pintype "bidirectional"))
      (node (ref "U1") (pin "54") (pinfunction "VBUS_54") (pintype "bidirectional"))
    )
    (net (code "86") (name "/VPP") (class "Default")
      (node (ref "J4") (pin "5") (pinfunction "5_5") (pintype "passive"))
      (node (ref "J5") (pin "1") (pinfunction "1_1") (pintype "passive"))
      (node (ref "R10") (pin "2") (pinfunction "2_2") (pintype "passive"))
      (node (ref "RESET") (pin "3") (pinfunction "3_3") (pintype "passive"))
      (node (ref "RESET") (pin "4") (pinfunction "4_4") (pintype "passive"))
      (node (ref "U1") (pin "13") (pinfunction "MCLR_13") (pintype "bidirectional"))
    )
    (net (code "87") (name "3.3V") (class "Default")
      (node (ref "3.3") (pin "1") (pinfunction "1_1") (pintype "passive"))
      (node (ref "C10") (pin "1") (pinfunction "1_1") (pintype "passive"))
      (node (ref "C11") (pin "1") (pinfunction "1_1") (pintype "passive"))
      (node (ref "C13") (pin "1") (pinfunction "1_1") (pintype "passive"))
      (node (ref "C6") (pin "1") (pinfunction "1_1") (pintype "passive"))
      (node (ref "C7") (pin "1") (pinfunction "1_1") (pintype "passive"))
      (node (ref "C8") (pin "1") (pinfunction "1_1") (pintype "passive"))
      (node (ref "C9") (pin "1") (pinfunction "1_1") (pintype "passive"))
      (node (ref "J3") (pin "3") (pinfunction "3_3") (pintype "passive"))
      (node (ref "J4") (pin "38") (pinfunction "38_38") (pintype "passive"))
      (node (ref "J5") (pin "2") (pinfunction "2_2") (pintype "passive"))
      (node (ref "R10") (pin "1") (pinfunction "1_1") (pintype "passive"))
      (node (ref "R11") (pin "2") (pinfunction "2_2") (pintype "passive"))
      (node (ref "R14") (pin "1") (pinfunction "1_1") (pintype "passive"))
      (node (ref "R3") (pin "1") (pinfunction "1_1") (pintype "passive"))
      (node (ref "R4") (pin "2") (pinfunction "2_2") (pintype "passive"))
      (node (ref "R5") (pin "1") (pinfunction "1_1") (pintype "passive"))
      (node (ref "R6") (pin "2") (pinfunction "2_2") (pintype "passive"))
      (node (ref "R7") (pin "2") (pinfunction "2_2") (pintype "passive"))
      (node (ref "R8") (pin "2") (pinfunction "2_2") (pintype "passive"))
      (node (ref "R9") (pin "2") (pinfunction "2_2") (pintype "passive"))
      (node (ref "U1") (pin "16") (pinfunction "VDD2_16") (pintype "bidirectional"))
      (node (ref "U1") (pin "2") (pinfunction "VDD1_2") (pintype "bidirectional"))
      (node (ref "U1") (pin "30") (pinfunction "AVDD_30") (pintype "bidirectional"))
      (node (ref "U1") (pin "37") (pinfunction "VDD3_37") (pintype "bidirectional"))
      (node (ref "U1") (pin "46") (pinfunction "VDD4_46") (pintype "bidirectional"))
      (node (ref "U1") (pin "55") (pinfunction "VUSB_55") (pintype "bidirectional"))
      (node (ref "U1") (pin "62") (pinfunction "VDD5_62") (pintype "bidirectional"))
      (node (ref "U1") (pin "86") (pinfunction "ENVREG_86") (pintype "bidirectional"))
      (node (ref "U2") (pin "2") (pinfunction "OUT_2") (pintype "output"))
    )
    (net (code "88") (name "5V") (class "Default")
      (node (ref "5") (pin "1") (pinfunction "1_1") (pintype "passive"))
      (node (ref "C12") (pin "1") (pinfunction "1_1") (pintype "passive"))
      (node (ref "F1") (pin "2") (pinfunction "2_2") (pintype "passive"))
      (node (ref "J3") (pin "2") (pinfunction "2_2") (pintype "passive"))
      (node (ref "J4") (pin "39") (pinfunction "39_39") (pintype "passive"))
      (node (ref "U2") (pin "3") (pinfunction "IN_3") (pintype "input"))
    )
    (net (code "89") (name "GND") (class "Default")
      (node (ref "C1") (pin "C") (pinfunction "-_C") (pintype "passive"))
      (node (ref "C10") (pin "2") (pinfunction "2_2") (pintype "passive"))
      (node (ref "C11") (pin "2") (pinfunction "2_2") (pintype "passive"))
      (node (ref "C12") (pin "2") (pinfunction "2_2") (pintype "passive"))
      (node (ref "C13") (pin "2") (pinfunction "2_2") (pintype "passive"))
      (node (ref "C14") (pin "1") (pinfunction "1_1") (pintype "passive"))
      (node (ref "C15") (pin "1") (pinfunction "1_1") (pintype "passive"))
      (node (ref "C16") (pin "2") (pinfunction "2_2") (pintype "passive"))
      (node (ref "C17") (pin "2") (pinfunction "2_2") (pintype "passive"))
      (node (ref "C2") (pin "2") (pinfunction "2_2") (pintype "passive"))
      (node (ref "C3") (pin "2") (pinfunction "2_2") (pintype "passive"))
      (node (ref "C4") (pin "2") (pinfunction "2_2") (pintype "passive"))
      (node (ref "C5") (pin "C") (pinfunction "-_C") (pintype "passive"))
      (node (ref "C6") (pin "2") (pinfunction "2_2") (pintype "passive"))
      (node (ref "C7") (pin "2") (pinfunction "2_2") (pintype "passive"))
      (node (ref "C8") (pin "2") (pinfunction "2_2") (pintype "passive"))
      (node (ref "C9") (pin "2") (pinfunction "2_2") (pintype "passive"))
      (node (ref "GND") (pin "1") (pinfunction "1_1") (pintype "passive"))
      (node (ref "J1") (pin "1") (pinfunction "1_1") (pintype "passive"))
      (node (ref "J2") (pin "1") (pinfunction "1_1") (pintype "passive"))
      (node (ref "J3") (pin "1") (pinfunction "1_1") (pintype "passive"))
      (node (ref "J4") (pin "40") (pinfunction "40_40") (pintype "passive"))
      (node (ref "J5") (pin "3") (pinfunction "3_3") (pintype "passive"))
      (node (ref "J6") (pin "5") (pinfunction "5_5") (pintype "passive"))
      (node (ref "J7") (pin "GND") (pinfunction "GND_GND") (pintype "bidirectional"))
      (node (ref "J8") (pin "G1") (pinfunction "P$1_G1") (pintype "bidirectional"))
      (node (ref "J8") (pin "G2") (pinfunction "P$2_G2") (pintype "bidirectional"))
      (node (ref "J8") (pin "G3") (pinfunction "P$3_G3") (pintype "bidirectional"))
      (node (ref "J8") (pin "G4") (pinfunction "SHIELD_G4") (pintype "bidirectional"))
      (node (ref "J8") (pin "GND") (pinfunction "GND_GND") (pintype "bidirectional"))
      (node (ref "PROGRAM") (pin "1") (pinfunction "1_1") (pintype "passive"))
      (node (ref "PROGRAM") (pin "2") (pinfunction "2_2") (pintype "passive"))
      (node (ref "PWR") (pin "C") (pinfunction "C_C") (pintype "passive"))
      (node (ref "R13") (pin "1") (pinfunction "1_1") (pintype "passive"))
      (node (ref "R15") (pin "1") (pinfunction "1_1") (pintype "passive"))
      (node (ref "RESET") (pin "1") (pinfunction "1_1") (pintype "passive"))
      (node (ref "RESET") (pin "2") (pinfunction "2_2") (pintype "passive"))
      (node (ref "U1") (pin "15") (pinfunction "VSS1_15") (pintype "bidirectional"))
      (node (ref "U1") (pin "31") (pinfunction "AVSS_31") (pintype "bidirectional"))
      (node (ref "U1") (pin "36") (pinfunction "VSS2_36") (pintype "bidirectional"))
      (node (ref "U1") (pin "45") (pinfunction "VSS3_45") (pintype "bidirectional"))
      (node (ref "U1") (pin "65") (pinfunction "VSS4_65") (pintype "bidirectional"))
      (node (ref "U1") (pin "75") (pinfunction "VSS6_75") (pintype "bidirectional"))
      (node (ref "USER") (pin "1") (pinfunction "1_1") (pintype "passive"))
      (node (ref "USER") (pin "2") (pinfunction "2_2") (pintype "passive"))
    )
    (net (code "90") (name "Net-(C1-+)") (class "Default")
      (node (ref "C1") (pin "A") (pinfunction "+_A") (pintype "passive"))
      (node (ref "D1") (pin "C") (pinfunction "C_C") (pintype "passive"))
      (node (ref "U3") (pin "3") (pinfunction "IN_3") (pintype "input"))
    )
    (net (code "91") (name "Net-(C5-+)") (class "Default")
      (node (ref "C4") (pin "1") (pinfunction "1_1") (pintype "passive"))
      (node (ref "C5") (pin "A") (pinfunction "+_A") (pintype "passive"))
      (node (ref "U1") (pin "85") (pinfunction "VCAP/VDDCORE_85") (pintype "bidirectional"))
    )
    (net (code "92") (name "Net-(D1-PadA)") (class "Default")
      (node (ref "D1") (pin "A") (pinfunction "A_A") (pintype "passive"))
      (node (ref "J1") (pin "2") (pinfunction "2_2") (pintype "passive"))
      (node (ref "J2") (pin "2") (pinfunction "2_2") (pintype "passive"))
    )
    (net (code "93") (name "Net-(F1-Pad1)") (class "Default")
      (node (ref "F1") (pin "1") (pinfunction "1_1") (pintype "passive"))
      (node (ref "PWR_SEL") (pin "2") (pinfunction "2_2") (pintype "bidirectional"))
      (node (ref "PWR_SEL") (pin "5") (pinfunction "5_5") (pintype "bidirectional"))
    )
    (net (code "94") (name "Net-(LED1-PadA)") (class "Default")
      (node (ref "LED1") (pin "A") (pinfunction "A_A") (pintype "passive"))
      (node (ref "R7") (pin "1") (pinfunction "1_1") (pintype "passive"))
    )
    (net (code "95") (name "Net-(LED2-PadA)") (class "Default")
      (node (ref "LED2") (pin "A") (pinfunction "A_A") (pintype "passive"))
      (node (ref "R6") (pin "1") (pinfunction "1_1") (pintype "passive"))
    )
    (net (code "96") (name "Net-(LED3-PadA)") (class "Default")
      (node (ref "LED3") (pin "A") (pinfunction "A_A") (pintype "passive"))
      (node (ref "R4") (pin "1") (pinfunction "1_1") (pintype "passive"))
    )
    (net (code "97") (name "Net-(PWR-PadA)") (class "Default")
      (node (ref "PWR") (pin "A") (pinfunction "A_A") (pintype "passive"))
      (node (ref "R11") (pin "1") (pinfunction "1_1") (pintype "passive"))
    )
    (net (code "98") (name "Net-(R8-Pad1)") (class "Default")
      (node (ref "R8") (pin "1") (pinfunction "1_1") (pintype "passive"))
      (node (ref "USB") (pin "A") (pinfunction "A_A") (pintype "passive"))
    )
    (net (code "99") (name "Net-(U2-ADJ)") (class "Default")
      (node (ref "R13") (pin "2") (pinfunction "2_2") (pintype "passive"))
      (node (ref "R14") (pin "2") (pinfunction "2_2") (pintype "passive"))
      (node (ref "U2") (pin "1") (pinfunction "ADJ_1") (pintype "input"))
    )
    (net (code "100") (name "Net-(U3-ADJ)") (class "Default")
      (node (ref "R15") (pin "2") (pinfunction "2_2") (pintype "passive"))
      (node (ref "R16") (pin "2") (pinfunction "2_2") (pintype "passive"))
      (node (ref "U3") (pin "1") (pinfunction "ADJ_1") (pintype "input"))
    )
  )
)
